# Sheet1.net
KiCad netlist of a schematic drawn in Altium Designer
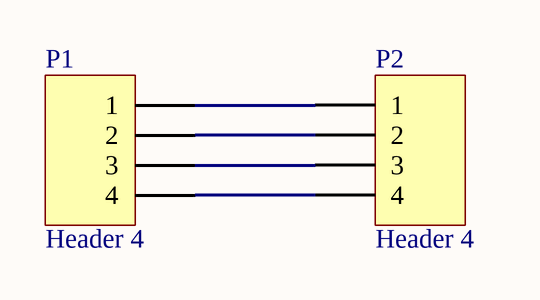
[diagram p0: Sheet1.SchDoc]

(export (version "E")
  (design (tool "Eeschema 10.0.6"))
  (components
    (comp (ref "P1")
      (value "Header 4")
      (footprint "HDR1X4")
      (description "Header, 4-Pin")
      (fields (field (name "PUBLISHER") "Altium Limited"))
      (libsource (lib "Miscellaneous Connectors") (part "Header 4"))
    )
    (comp (ref "P2")
      (value "Header 4")
      (footprint "HDR1X4")
      (description "Header, 4-Pin")
      (fields (field (name "PUBLISHER") "Altium Limited"))
      (libsource (lib "") (part "Header 4_1"))
    )
  )
  (nets
    (net (code "1") (name "Net-(P1-Pad1)") (class "Default")
      (node (ref "P1") (pin "1") (pinfunction "1_1") (pintype "passive"))
      (node (ref "P2") (pin "1") (pinfunction "1_1") (pintype "passive"))
    )
    (net (code "2") (name "Net-(P1-Pad2)") (class "Default")
      (node (ref "P1") (pin "2") (pinfunction "2_2") (pintype "passive"))
      (node (ref "P2") (pin "2") (pinfunction "2_2") (pintype "passive"))
    )
    (net (code "3") (name "Net-(P1-Pad3)") (class "Default")
      (node (ref "P1") (pin "3") (pinfunction "3_3") (pintype "passive"))
      (node (ref "P2") (pin "3") (pinfunction "3_3") (pintype "passive"))
    )
    (net (code "4") (name "Net-(P1-Pad4)") (class "Default")
      (node (ref "P1") (pin "4") (pinfunction "4_4") (pintype "passive"))
      (node (ref "P2") (pin "4") (pinfunction "4_4") (pintype "passive"))
    )
  )
)
